# controller.net
KiCad netlist of a schematic drawn in EAGLE
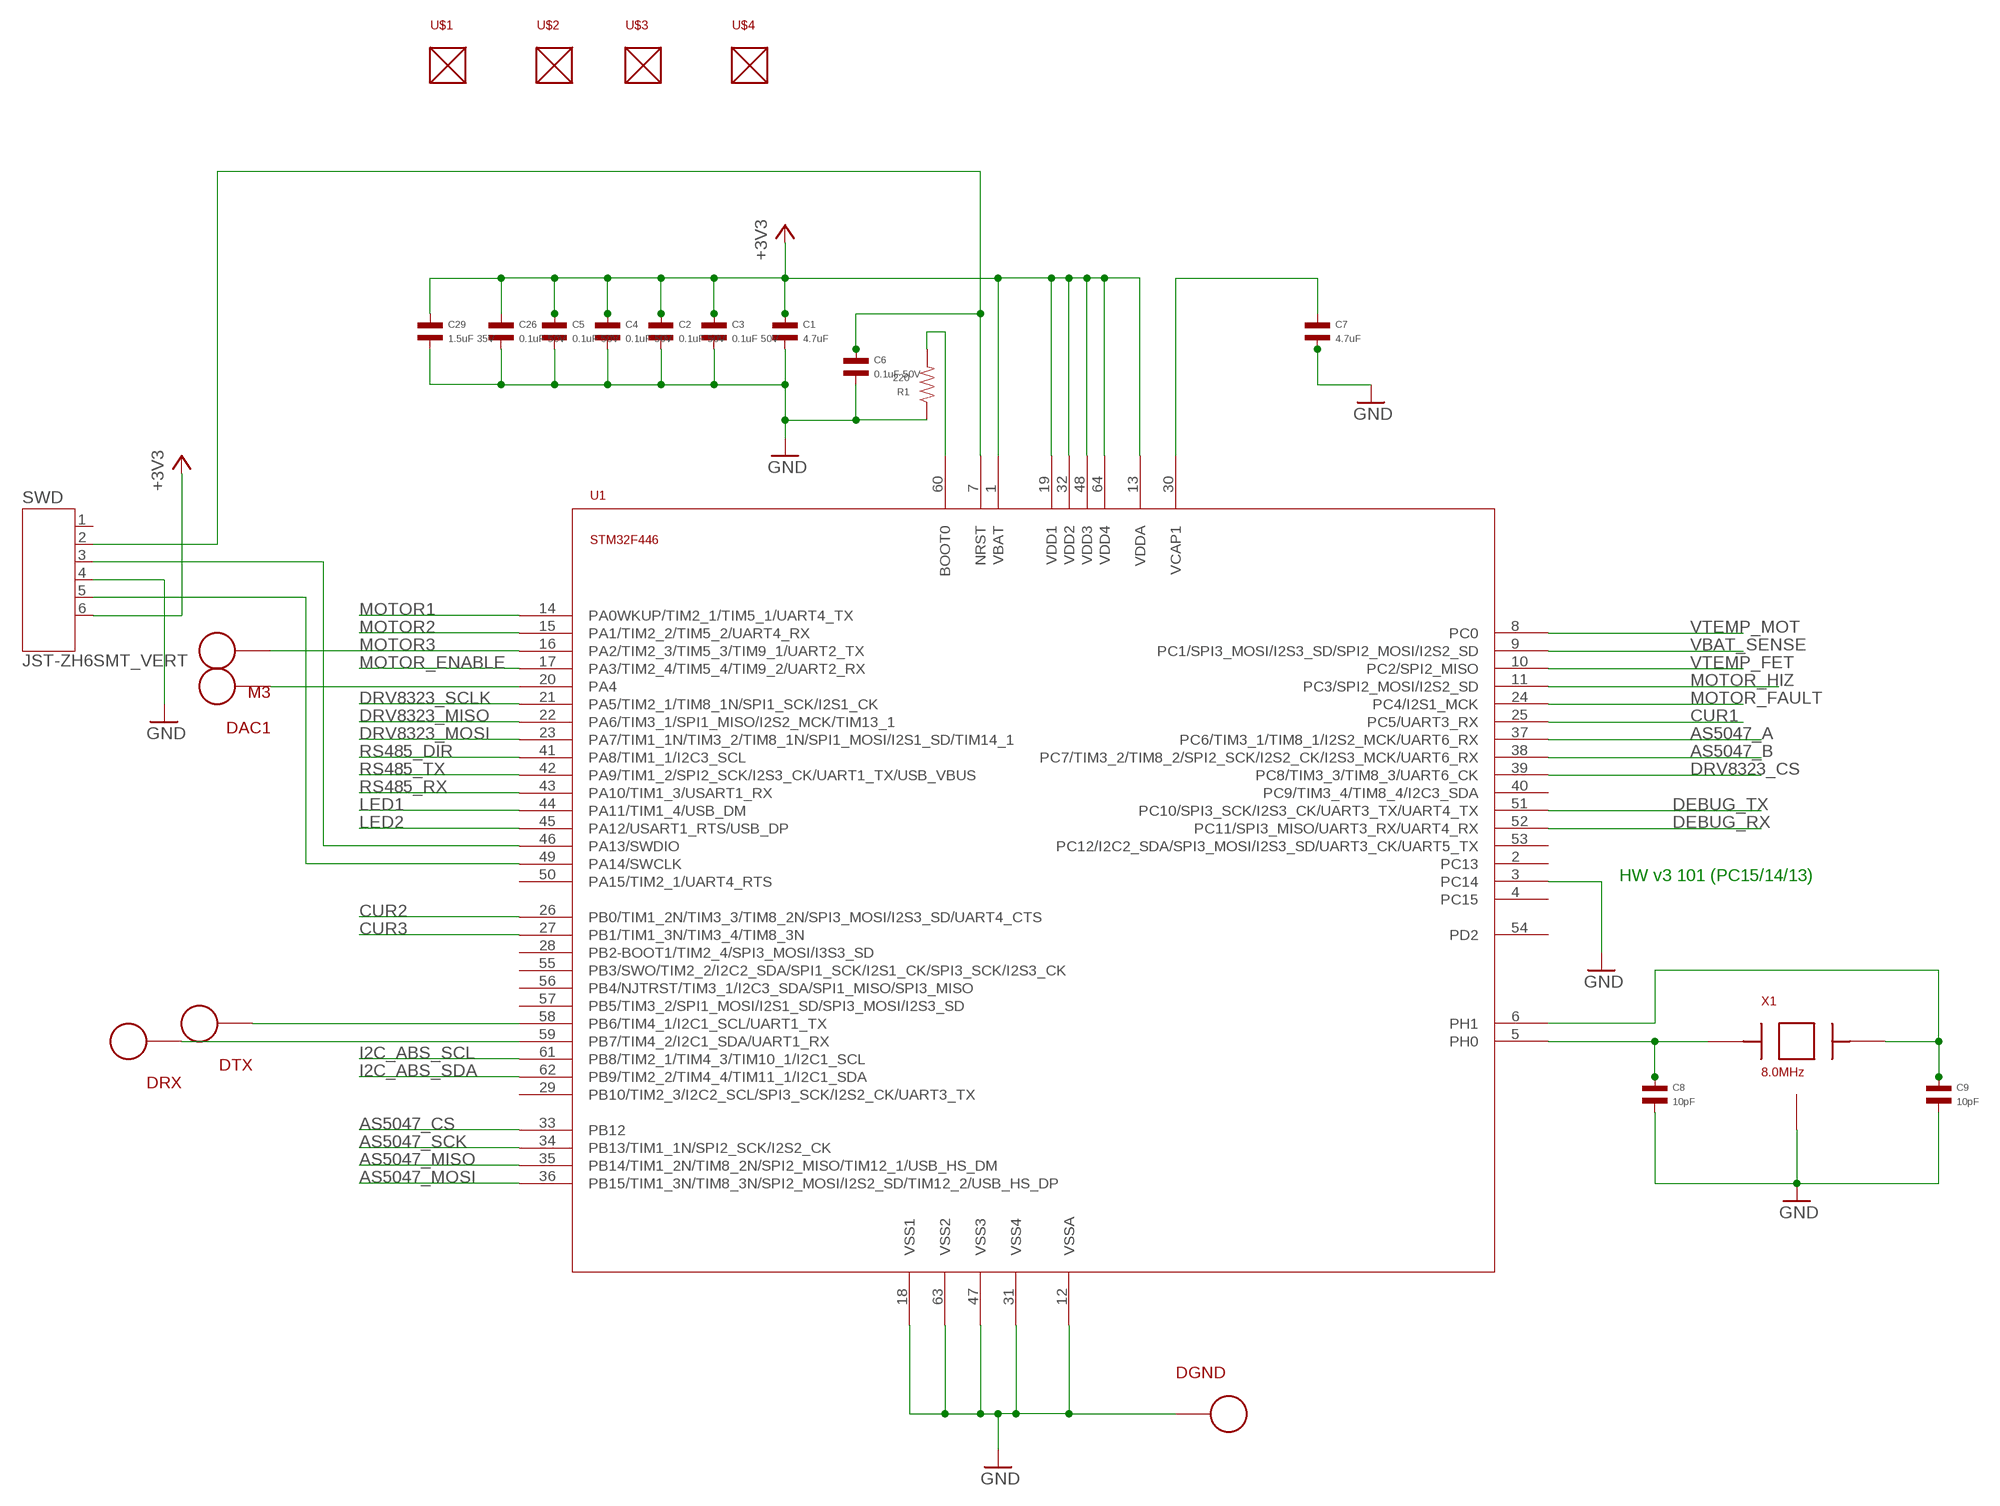
[diagram p0: schematic, sheet 1, part 1 of 2]
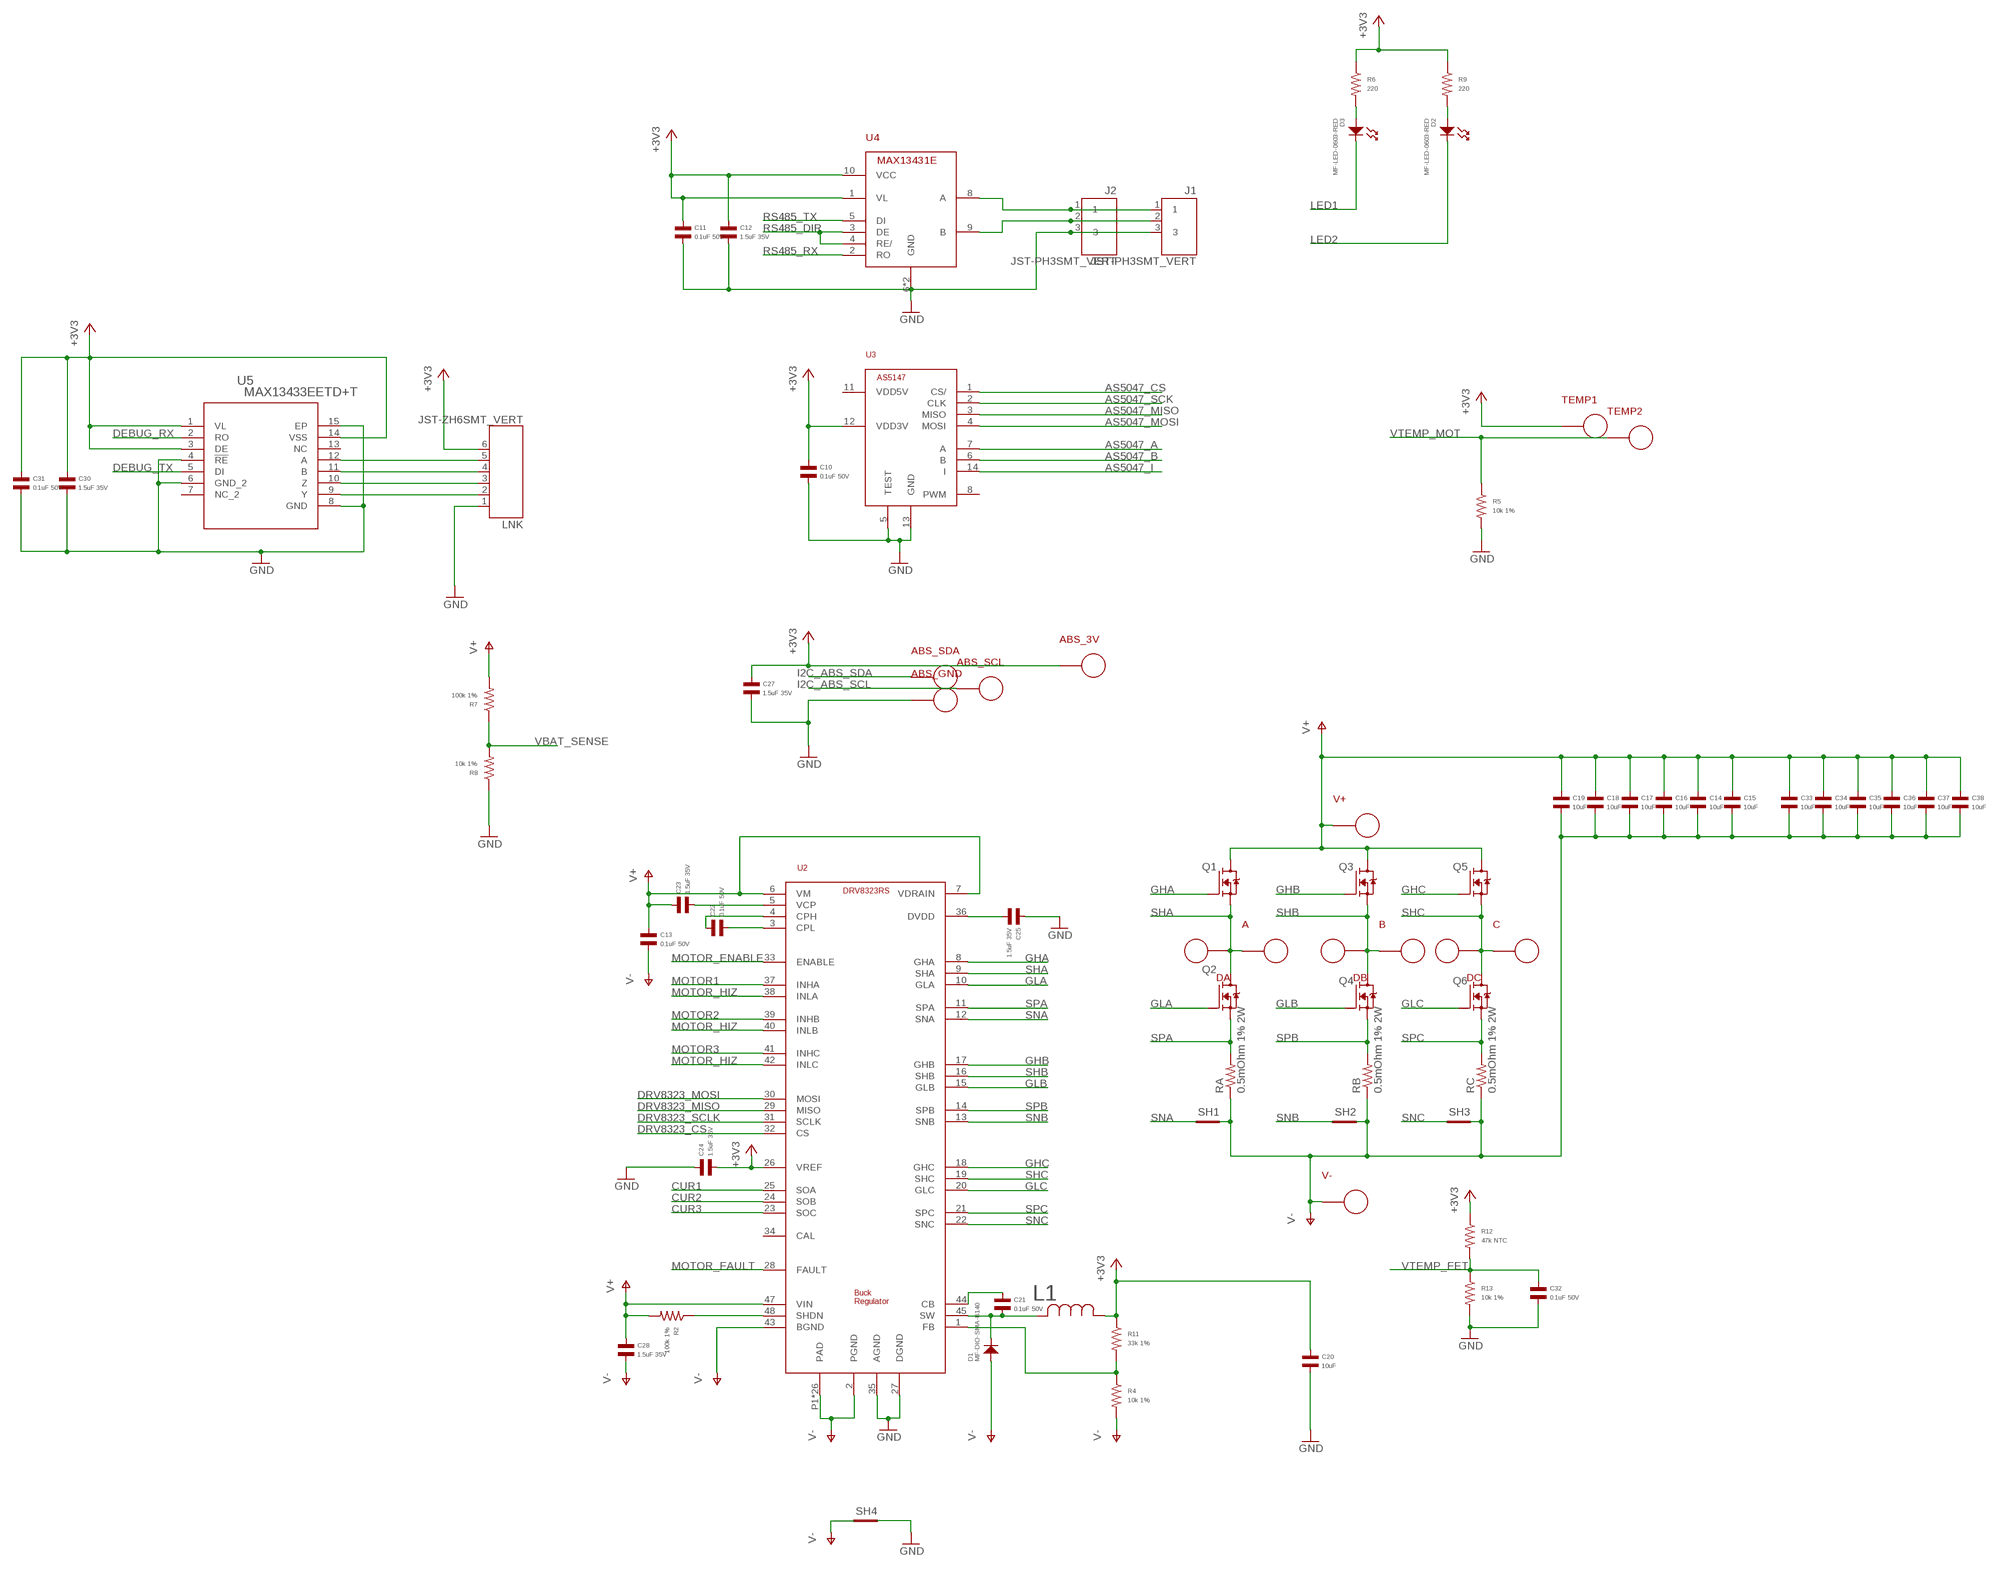
[diagram p1: schematic, sheet 1, part 2 of 2]

(export (version "E")
  (design (tool "Eeschema 10.0.6"))
  (components
    (comp (ref "A")
      (value "PAD")
      (footprint "eagle-import:18AWG_PAD")
      (libsource (lib "eagle-import") (part "PAD"))
    )
    (comp (ref "ABS_3V")
      (value "PAD24AWG_PAD")
      (footprint "eagle-import:24AWG_PAD")
      (libsource (lib "eagle-import") (part "PAD24AWG_PAD"))
    )
    (comp (ref "ABS_GND")
      (value "PAD24AWG_PAD")
      (footprint "eagle-import:24AWG_PAD")
      (libsource (lib "eagle-import") (part "PAD24AWG_PAD"))
    )
    (comp (ref "ABS_SCL")
      (value "PAD24AWG_PAD")
      (footprint "eagle-import:24AWG_PAD")
      (libsource (lib "eagle-import") (part "PAD24AWG_PAD"))
    )
    (comp (ref "ABS_SDA")
      (value "PAD24AWG_PAD")
      (footprint "eagle-import:24AWG_PAD")
      (libsource (lib "eagle-import") (part "PAD24AWG_PAD"))
    )
    (comp (ref "B")
      (value "PAD")
      (footprint "eagle-import:18AWG_PAD")
      (libsource (lib "eagle-import") (part "PAD"))
    )
    (comp (ref "C")
      (value "PAD")
      (footprint "eagle-import:18AWG_PAD")
      (libsource (lib "eagle-import") (part "PAD"))
    )
    (comp (ref "C1")
      (value "4.7uF")
      (footprint "eagle-import:C0603")
      (fields (field (name "MF") "Samsung Electro-Mechanics") (field (name "MPN") "CL10A475MP8NNNC"))
      (libsource (lib "eagle-import") (part "CAPACITOR_NP_0603"))
    )
    (comp (ref "C2")
      (value "0.1uF 50V")
      (footprint "eagle-import:C0402")
      (fields (field (name "MF") "TDK") (field (name "MPN") "CGA2B3X7R1H104K050BB"))
      (libsource (lib "eagle-import") (part "CAPACITOR_NP_0402"))
    )
    (comp (ref "C3")
      (value "0.1uF 50V")
      (footprint "eagle-import:C0402")
      (fields (field (name "MF") "TDK") (field (name "MPN") "CGA2B3X7R1H104K050BB"))
      (libsource (lib "eagle-import") (part "CAPACITOR_NP_0402"))
    )
    (comp (ref "C4")
      (value "0.1uF 50V")
      (footprint "eagle-import:C0402")
      (fields (field (name "MF") "TDK") (field (name "MPN") "CGA2B3X7R1H104K050BB"))
      (libsource (lib "eagle-import") (part "CAPACITOR_NP_0402"))
    )
    (comp (ref "C5")
      (value "0.1uF 50V")
      (footprint "eagle-import:C0402")
      (fields (field (name "MF") "TDK") (field (name "MPN") "CGA2B3X7R1H104K050BB"))
      (libsource (lib "eagle-import") (part "CAPACITOR_NP_0402"))
    )
    (comp (ref "C6")
      (value "0.1uF 50V")
      (footprint "eagle-import:C0402")
      (fields (field (name "MF") "TDK") (field (name "MPN") "CGA2B3X7R1H104K050BB"))
      (libsource (lib "eagle-import") (part "CAPACITOR_NP_0402"))
    )
    (comp (ref "C7")
      (value "4.7uF")
      (footprint "eagle-import:C0603")
      (fields (field (name "MF") "Samsung Electro-Mechanics") (field (name "MPN") "CL10A475MP8NNNC"))
      (libsource (lib "eagle-import") (part "CAPACITOR_NP_0603"))
    )
    (comp (ref "C8")
      (value "10pF")
      (footprint "eagle-import:C0402")
      (fields (field (name "MF") "Samsung Electro-Mechanics") (field (name "MPN") "CL05C100JB51PNC"))
      (libsource (lib "eagle-import") (part "CAPACITOR_NP_0402"))
    )
    (comp (ref "C9")
      (value "10pF")
      (footprint "eagle-import:C0402")
      (fields (field (name "MF") "Samsung Electro-Mechanics") (field (name "MPN") "CL05C100JB51PNC"))
      (libsource (lib "eagle-import") (part "CAPACITOR_NP_0402"))
    )
    (comp (ref "C10")
      (value "0.1uF 50V")
      (footprint "eagle-import:C0402")
      (fields (field (name "MF") "TDK") (field (name "MPN") "CGA2B3X7R1H104K050BB"))
      (libsource (lib "eagle-import") (part "CAPACITOR_NP_0402"))
    )
    (comp (ref "C11")
      (value "0.1uF 50V")
      (footprint "eagle-import:C0402")
      (fields (field (name "MF") "TDK") (field (name "MPN") "CGA2B3X7R1H104K050BB"))
      (libsource (lib "eagle-import") (part "CAPACITOR_NP_0402"))
    )
    (comp (ref "C12")
      (value "1.5uF 35V")
      (footprint "eagle-import:C0402")
      (fields (field (name "MF") "TDK") (field (name "MPN") "C1005X5R1V155M050BC"))
      (libsource (lib "eagle-import") (part "CAPACITOR_NP_0402"))
    )
    (comp (ref "C13")
      (value "0.1uF 50V")
      (footprint "eagle-import:C0402")
      (fields (field (name "MF") "TDK") (field (name "MPN") "CGA2B3X7R1H104K050BB"))
      (libsource (lib "eagle-import") (part "CAPACITOR_NP_0402"))
    )
    (comp (ref "C14")
      (value "10uF")
      (footprint "eagle-import:C1206")
      (fields (field (name "MF") "TDK") (field (name "MPN") "CGA5L1X7R1V106K160AC"))
      (libsource (lib "eagle-import") (part "CAPACITOR_NP_1206"))
    )
    (comp (ref "C15")
      (value "10uF")
      (footprint "eagle-import:C1206")
      (fields (field (name "MF") "TDK") (field (name "MPN") "CGA5L1X7R1V106K160AC"))
      (libsource (lib "eagle-import") (part "CAPACITOR_NP_1206"))
    )
    (comp (ref "C16")
      (value "10uF")
      (footprint "eagle-import:C1206")
      (fields (field (name "MF") "TDK") (field (name "MPN") "CGA5L1X7R1V106K160AC"))
      (libsource (lib "eagle-import") (part "CAPACITOR_NP_1206"))
    )
    (comp (ref "C17")
      (value "10uF")
      (footprint "eagle-import:C1206")
      (fields (field (name "MF") "TDK") (field (name "MPN") "CGA5L1X7R1V106K160AC"))
      (libsource (lib "eagle-import") (part "CAPACITOR_NP_1206"))
    )
    (comp (ref "C18")
      (value "10uF")
      (footprint "eagle-import:C1206")
      (fields (field (name "MF") "TDK") (field (name "MPN") "CGA5L1X7R1V106K160AC"))
      (libsource (lib "eagle-import") (part "CAPACITOR_NP_1206"))
    )
    (comp (ref "C19")
      (value "10uF")
      (footprint "eagle-import:C1206")
      (fields (field (name "MF") "TDK") (field (name "MPN") "CGA5L1X7R1V106K160AC"))
      (libsource (lib "eagle-import") (part "CAPACITOR_NP_1206"))
    )
    (comp (ref "C20")
      (value "10uF")
      (footprint "eagle-import:C1206")
      (fields (field (name "MF") "TDK") (field (name "MPN") "CGA5L1X7R1V106K160AC"))
      (libsource (lib "eagle-import") (part "CAPACITOR_NP_1206"))
    )
    (comp (ref "C21")
      (value "0.1uF 50V")
      (footprint "eagle-import:C0402")
      (fields (field (name "MF") "TDK") (field (name "MPN") "CGA2B3X7R1H104K050BB"))
      (libsource (lib "eagle-import") (part "CAPACITOR_NP_0402"))
    )
    (comp (ref "C22")
      (value "0.1uF 50V")
      (footprint "eagle-import:C0402")
      (fields (field (name "MF") "TDK") (field (name "MPN") "CGA2B3X7R1H104K050BB"))
      (libsource (lib "eagle-import") (part "CAPACITOR_NP_0402"))
    )
    (comp (ref "C23")
      (value "1.5uF 35V")
      (footprint "eagle-import:C0402")
      (fields (field (name "MF") "TDK") (field (name "MPN") "C1005X5R1V155M050BC"))
      (libsource (lib "eagle-import") (part "CAPACITOR_NP_0402"))
    )
    (comp (ref "C24")
      (value "1.5uF 35V")
      (footprint "eagle-import:C0402")
      (fields (field (name "MF") "TDK") (field (name "MPN") "C1005X5R1V155M050BC"))
      (libsource (lib "eagle-import") (part "CAPACITOR_NP_0402"))
    )
    (comp (ref "C25")
      (value "1.5uF 35V")
      (footprint "eagle-import:C0402")
      (fields (field (name "MF") "TDK") (field (name "MPN") "C1005X5R1V155M050BC"))
      (libsource (lib "eagle-import") (part "CAPACITOR_NP_0402"))
    )
    (comp (ref "C26")
      (value "0.1uF 50V")
      (footprint "eagle-import:C0402")
      (fields (field (name "MF") "TDK") (field (name "MPN") "CGA2B3X7R1H104K050BB"))
      (libsource (lib "eagle-import") (part "CAPACITOR_NP_0402"))
    )
    (comp (ref "C27")
      (value "1.5uF 35V")
      (footprint "eagle-import:C0402")
      (fields (field (name "MF") "TDK") (field (name "MPN") "C1005X5R1V155M050BC"))
      (libsource (lib "eagle-import") (part "CAPACITOR_NP_0402"))
    )
    (comp (ref "C28")
      (value "1.5uF 35V")
      (footprint "eagle-import:C0402")
      (fields (field (name "MF") "TDK") (field (name "MPN") "C1005X5R1V155M050BC"))
      (libsource (lib "eagle-import") (part "CAPACITOR_NP_0402"))
    )
    (comp (ref "C29")
      (value "1.5uF 35V")
      (footprint "eagle-import:C0402")
      (fields (field (name "MF") "TDK") (field (name "MPN") "C1005X5R1V155M050BC"))
      (libsource (lib "eagle-import") (part "CAPACITOR_NP_0402"))
    )
    (comp (ref "C30")
      (value "1.5uF 35V")
      (footprint "eagle-import:C0402")
      (fields (field (name "MF") "TDK") (field (name "MPN") "C1005X5R1V155M050BC"))
      (libsource (lib "eagle-import") (part "CAPACITOR_NP_0402"))
    )
    (comp (ref "C31")
      (value "0.1uF 50V")
      (footprint "eagle-import:C0402")
      (fields (field (name "MF") "TDK") (field (name "MPN") "CGA2B3X7R1H104K050BB"))
      (libsource (lib "eagle-import") (part "CAPACITOR_NP_0402"))
    )
    (comp (ref "C32")
      (value "0.1uF 50V")
      (footprint "eagle-import:C0402")
      (fields (field (name "MF") "TDK") (field (name "MPN") "CGA2B3X7R1H104K050BB"))
      (libsource (lib "eagle-import") (part "CAPACITOR_NP_0402"))
    )
    (comp (ref "C33")
      (value "10uF")
      (footprint "eagle-import:C1206")
      (fields (field (name "MF") "TDK") (field (name "MPN") "CGA5L1X7R1V106K160AC"))
      (libsource (lib "eagle-import") (part "CAPACITOR_NP_1206"))
    )
    (comp (ref "C34")
      (value "10uF")
      (footprint "eagle-import:C1206")
      (fields (field (name "MF") "TDK") (field (name "MPN") "CGA5L1X7R1V106K160AC"))
      (libsource (lib "eagle-import") (part "CAPACITOR_NP_1206"))
    )
    (comp (ref "C35")
      (value "10uF")
      (footprint "eagle-import:C1206")
      (fields (field (name "MF") "TDK") (field (name "MPN") "CGA5L1X7R1V106K160AC"))
      (libsource (lib "eagle-import") (part "CAPACITOR_NP_1206"))
    )
    (comp (ref "C36")
      (value "10uF")
      (footprint "eagle-import:C1206")
      (fields (field (name "MF") "TDK") (field (name "MPN") "CGA5L1X7R1V106K160AC"))
      (libsource (lib "eagle-import") (part "CAPACITOR_NP_1206"))
    )
    (comp (ref "C37")
      (value "10uF")
      (footprint "eagle-import:C1206")
      (fields (field (name "MF") "TDK") (field (name "MPN") "CGA5L1X7R1V106K160AC"))
      (libsource (lib "eagle-import") (part "CAPACITOR_NP_1206"))
    )
    (comp (ref "C38")
      (value "10uF")
      (footprint "eagle-import:C1206")
      (fields (field (name "MF") "TDK") (field (name "MPN") "CGA5L1X7R1V106K160AC"))
      (libsource (lib "eagle-import") (part "CAPACITOR_NP_1206"))
    )
    (comp (ref "D1")
      (value "MF-DIO-SMA-B140")
      (footprint "eagle-import:SMA")
      (fields (field (name "HOUSEPART") "YES"))
      (libsource (lib "eagle-import") (part "DIODES_SMA_B140"))
    )
    (comp (ref "D2")
      (value "MF-LED-0603-RED")
      (footprint "eagle-import:LED0603")
      (fields (field (name "HOUSEPART") "YES"))
      (libsource (lib "eagle-import") (part "LED_SINGLE-0603-RED"))
    )
    (comp (ref "D3")
      (value "MF-LED-0603-RED")
      (footprint "eagle-import:LED0603")
      (fields (field (name "HOUSEPART") "YES"))
      (libsource (lib "eagle-import") (part "LED_SINGLE-0603-RED"))
    )
    (comp (ref "DA")
      (value "PAD24AWG_PAD")
      (footprint "eagle-import:24AWG_PAD")
      (libsource (lib "eagle-import") (part "PAD24AWG_PAD"))
    )
    (comp (ref "DAC1")
      (value "PAD24AWG_PAD")
      (footprint "eagle-import:24AWG_PAD")
      (libsource (lib "eagle-import") (part "PAD24AWG_PAD"))
    )
    (comp (ref "DB")
      (value "PAD24AWG_PAD")
      (footprint "eagle-import:24AWG_PAD")
      (libsource (lib "eagle-import") (part "PAD24AWG_PAD"))
    )
    (comp (ref "DC")
      (value "PAD24AWG_PAD")
      (footprint "eagle-import:24AWG_PAD")
      (libsource (lib "eagle-import") (part "PAD24AWG_PAD"))
    )
    (comp (ref "DGND")
      (value "PAD24AWG_PAD")
      (footprint "eagle-import:24AWG_PAD")
      (libsource (lib "eagle-import") (part "PAD24AWG_PAD"))
    )
    (comp (ref "DRX")
      (value "PAD24AWG_PAD")
      (footprint "eagle-import:24AWG_PAD")
      (libsource (lib "eagle-import") (part "PAD24AWG_PAD"))
    )
    (comp (ref "DTX")
      (value "PAD24AWG_PAD")
      (footprint "eagle-import:24AWG_PAD")
      (libsource (lib "eagle-import") (part "PAD24AWG_PAD"))
    )
    (comp (ref "J1")
      (value "JST-PH3SMT_VERT")
      (footprint "eagle-import:JST_B3B_PH-SM4-TB(LF)(SN)")
      (fields (field (name "MF") "JST") (field (name "MPN") "B3B-PH-SM4-TB(LF)(SN)"))
      (libsource (lib "eagle-import") (part "JST-PH3SMT_VERT"))
    )
    (comp (ref "J2")
      (value "JST-PH3SMT_VERT")
      (footprint "eagle-import:JST_B3B_PH-SM4-TB(LF)(SN)")
      (fields (field (name "MF") "JST") (field (name "MPN") "B3B-PH-SM4-TB(LF)(SN)"))
      (libsource (lib "eagle-import") (part "JST-PH3SMT_VERT"))
    )
    (comp (ref "L1")
      (value "SRN4018-220M")
      (footprint "eagle-import:IND_BOURNS_SRN4018")
      (fields (field (name "MANUFACTURER_PART_NUMBER") "SRN4018220M"))
      (libsource (lib "eagle-import") (part "SRN4018-220M"))
    )
    (comp (ref "LNK")
      (value "JST-ZH6SMT_VERT")
      (footprint "eagle-import:JST_B6B-ZR-SM4-TF(LF)(SN)")
      (fields (field (name "MF") "JST") (field (name "MPN") "B6B-ZR-SM4-TF(LF)(SN)"))
      (libsource (lib "eagle-import") (part "JST-ZH6SMT_VERT"))
    )
    (comp (ref "M3")
      (value "PAD24AWG_PAD")
      (footprint "eagle-import:24AWG_PAD")
      (libsource (lib "eagle-import") (part "PAD24AWG_PAD"))
    )
    (comp (ref "Q1")
      (value "TPN1R603PL")
      (footprint "eagle-import:TSON_ADVANCE_8")
      (fields (field (name "MF") "Toshiba") (field (name "MPN") "TPN1R603PL,L1Q"))
      (libsource (lib "eagle-import") (part "TPN1R603PL"))
    )
    (comp (ref "Q2")
      (value "TPN1R603PL")
      (footprint "eagle-import:TSON_ADVANCE_8")
      (fields (field (name "MF") "Toshiba") (field (name "MPN") "TPN1R603PL,L1Q"))
      (libsource (lib "eagle-import") (part "TPN1R603PL"))
    )
    (comp (ref "Q3")
      (value "TPN1R603PL")
      (footprint "eagle-import:TSON_ADVANCE_8")
      (fields (field (name "MF") "Toshiba") (field (name "MPN") "TPN1R603PL,L1Q"))
      (libsource (lib "eagle-import") (part "TPN1R603PL"))
    )
    (comp (ref "Q4")
      (value "TPN1R603PL")
      (footprint "eagle-import:TSON_ADVANCE_8")
      (fields (field (name "MF") "Toshiba") (field (name "MPN") "TPN1R603PL,L1Q"))
      (libsource (lib "eagle-import") (part "TPN1R603PL"))
    )
    (comp (ref "Q5")
      (value "TPN1R603PL")
      (footprint "eagle-import:TSON_ADVANCE_8")
      (fields (field (name "MF") "Toshiba") (field (name "MPN") "TPN1R603PL,L1Q"))
      (libsource (lib "eagle-import") (part "TPN1R603PL"))
    )
    (comp (ref "Q6")
      (value "TPN1R603PL")
      (footprint "eagle-import:TSON_ADVANCE_8")
      (fields (field (name "MF") "Toshiba") (field (name "MPN") "TPN1R603PL,L1Q"))
      (libsource (lib "eagle-import") (part "TPN1R603PL"))
    )
    (comp (ref "R1")
      (value "220")
      (footprint "eagle-import:R0402")
      (fields (field (name "HOUSEPART") "1") (field (name "MPN") "MF-RES-0402-220"))
      (libsource (lib "eagle-import") (part "RESISTOR_0402"))
    )
    (comp (ref "R2")
      (value "100k 1%")
      (footprint "eagle-import:R0402")
      (fields (field (name "MF") "Panasonic") (field (name "MPN") "ERJ-2RKF1003X"))
      (libsource (lib "eagle-import") (part "RESISTOR_0402"))
    )
    (comp (ref "R4")
      (value "10k 1%")
      (footprint "eagle-import:R0402")
      (fields (field (name "MF") "Panasonic") (field (name "MPN") "ERJ-2RKF1002X"))
      (libsource (lib "eagle-import") (part "RESISTOR_0402"))
    )
    (comp (ref "R5")
      (value "10k 1%")
      (footprint "eagle-import:R0402")
      (fields (field (name "MF") "Panasonic") (field (name "MPN") "ERJ-2RKF1002X"))
      (libsource (lib "eagle-import") (part "RESISTOR_0402"))
    )
    (comp (ref "R6")
      (value "220")
      (footprint "eagle-import:R0402")
      (fields (field (name "HOUSEPART") "1") (field (name "MPN") "MF-RES-0402-220"))
      (libsource (lib "eagle-import") (part "RESISTOR_0402"))
    )
    (comp (ref "R7")
      (value "100k 1%")
      (footprint "eagle-import:R0402")
      (fields (field (name "MF") "Panasonic") (field (name "MPN") "ERJ-2RKF1003X"))
      (libsource (lib "eagle-import") (part "RESISTOR_0402"))
    )
    (comp (ref "R8")
      (value "10k 1%")
      (footprint "eagle-import:R0402")
      (fields (field (name "MF") "Panasonic") (field (name "MPN") "ERJ-2RKF1002X"))
      (libsource (lib "eagle-import") (part "RESISTOR_0402"))
    )
    (comp (ref "R9")
      (value "220")
      (footprint "eagle-import:R0402")
      (fields (field (name "HOUSEPART") "1") (field (name "MPN") "MF-RES-0402-220"))
      (libsource (lib "eagle-import") (part "RESISTOR_0402"))
    )
    (comp (ref "R11")
      (value "33k 1%")
      (footprint "eagle-import:R0402")
      (fields (field (name "MF") "Panasonic") (field (name "MPN") "ERJ-2RKF3302X"))
      (libsource (lib "eagle-import") (part "RESISTOR_0402"))
    )
    (comp (ref "R12")
      (value "47k NTC")
      (footprint "eagle-import:R0402")
      (fields (field (name "MF") "Murata") (field (name "MPN") "NCP15WB473F03RC"))
      (libsource (lib "eagle-import") (part "RESISTOR_0402"))
    )
    (comp (ref "R13")
      (value "10k 1%")
      (footprint "eagle-import:R0402")
      (fields (field (name "MF") "Panasonic") (field (name "MPN") "ERJ-2RKF1002X"))
      (libsource (lib "eagle-import") (part "RESISTOR_0402"))
    )
    (comp (ref "RA")
      (value "0.5mOhm 1% 2W")
      (footprint "eagle-import:M1206")
      (fields (field (name "MF") "Stackpole Electronics") (field (name "MPN") "HCS1206FTL500"))
      (libsource (lib "eagle-import") (part "R-US_M1206"))
    )
    (comp (ref "RB")
      (value "0.5mOhm 1% 2W")
      (footprint "eagle-import:M1206")
      (fields (field (name "MF") "Stackpole Electronics") (field (name "MPN") "HCS1206FTL500"))
      (libsource (lib "eagle-import") (part "R-US_M1206"))
    )
    (comp (ref "RC")
      (value "0.5mOhm 1% 2W")
      (footprint "eagle-import:M1206")
      (fields (field (name "MF") "Stackpole Electronics") (field (name "MPN") "HCS1206FTL500"))
      (libsource (lib "eagle-import") (part "R-US_M1206"))
    )
    (comp (ref "SH1")
      (value "SHORTT5")
      (footprint "eagle-import:SHORT_TOP-50")
      (libsource (lib "eagle-import") (part "SHORTT5"))
    )
    (comp (ref "SH2")
      (value "SHORTT5")
      (footprint "eagle-import:SHORT_TOP-50")
      (libsource (lib "eagle-import") (part "SHORTT5"))
    )
    (comp (ref "SH3")
      (value "SHORTT5")
      (footprint "eagle-import:SHORT_TOP-50")
      (libsource (lib "eagle-import") (part "SHORTT5"))
    )
    (comp (ref "SH4")
      (value "SHORTBIG")
      (footprint "eagle-import:SHORT_TOP-BIG")
      (libsource (lib "eagle-import") (part "SHORTBIG"))
    )
    (comp (ref "SWD")
      (value "JST-ZH6SMT_VERT")
      (footprint "eagle-import:JST_B6B-ZR-SM4-TF(LF)(SN)")
      (fields (field (name "MF") "JST") (field (name "MPN") "B6B-ZR-SM4-TF(LF)(SN)"))
      (libsource (lib "eagle-import") (part "JST-ZH6SMT_VERT"))
    )
    (comp (ref "TEMP1")
      (value "PAD24AWG_PAD")
      (footprint "eagle-import:24AWG_PAD")
      (libsource (lib "eagle-import") (part "PAD24AWG_PAD"))
    )
    (comp (ref "TEMP2")
      (value "PAD24AWG_PAD")
      (footprint "eagle-import:24AWG_PAD")
      (libsource (lib "eagle-import") (part "PAD24AWG_PAD"))
    )
    (comp (ref "U$1")
      (value "MOUNTM2")
      (footprint "eagle-import:M2MOUNT")
      (libsource (lib "eagle-import") (part "MOUNTM2"))
    )
    (comp (ref "U$2")
      (value "MOUNTM2")
      (footprint "eagle-import:M2MOUNT")
      (libsource (lib "eagle-import") (part "MOUNTM2"))
    )
    (comp (ref "U$3")
      (value "MOUNTM2")
      (footprint "eagle-import:M2MOUNT")
      (libsource (lib "eagle-import") (part "MOUNTM2"))
    )
    (comp (ref "U$4")
      (value "MOUNTM2")
      (footprint "eagle-import:M2MOUNT")
      (libsource (lib "eagle-import") (part "MOUNTM2"))
    )
    (comp (ref "U1")
      (value "STM32F4R_64PIN")
      (footprint "eagle-import:LQFP64")
      (fields (field (name "MF") "ST") (field (name "MPN") "STM32F446RET6"))
      (libsource (lib "eagle-import") (part "STM32F4R_64PIN"))
    )
    (comp (ref "U2")
      (value "DRV8323RS")
      (footprint "eagle-import:PVQFN-N48")
      (fields (field (name "MF") "TI") (field (name "MPN") "DRV8323RSRGZR"))
      (libsource (lib "eagle-import") (part "DRV8323RS"))
    )
    (comp (ref "U3")
      (value "AS5147")
      (footprint "eagle-import:TSSOP14")
      (fields (field (name "MF") "AMS") (field (name "MPN") "AS5047P-ATSM"))
      (libsource (lib "eagle-import") (part "AS5147"))
    )
    (comp (ref "U4")
      (value "MAX13431E")
      (footprint "eagle-import:TDFN10")
      (fields (field (name "MF") "Maxim") (field (name "MPN") "MAX13431EETB+T"))
      (libsource (lib "eagle-import") (part "MAX13431E"))
    )
    (comp (ref "U5")
      (value "MAX13433EETD+T")
      (footprint "eagle-import:21-0137I_T1433-1")
      (fields (field (name "MF") "Maxim"))
      (libsource (lib "eagle-import") (part "MAX13433EETD+T"))
    )
    (comp (ref "V+")
      (value "PAD12AWG_PAD")
      (footprint "eagle-import:12AWG_PAD")
      (libsource (lib "eagle-import") (part "PAD12AWG_PAD"))
    )
    (comp (ref "V-")
      (value "PAD12AWG_PAD")
      (footprint "eagle-import:12AWG_PAD")
      (libsource (lib "eagle-import") (part "PAD12AWG_PAD"))
    )
    (comp (ref "X1")
      (value "8.0MHz")
      (footprint "eagle-import:ABM3B")
      (fields (field (name "MF") "Abracon") (field (name "MPN") "ABM3B-8.000MHZ-10-1-U-T"))
      (libsource (lib "eagle-import") (part "CRYSTALABM3B"))
    )
  )
  (nets
    (net (code "1") (name "+3V3") (class "Default")
      (node (ref "ABS_3V") (pin "P$1") (pinfunction "P$1_P$1") (pintype "bidirectional"))
      (node (ref "C1") (pin "P$1") (pinfunction "P$1_P$1") (pintype "passive"))
      (node (ref "C10") (pin "P$1") (pinfunction "P$1_P$1") (pintype "passive"))
      (node (ref "C11") (pin "P$1") (pinfunction "P$1_P$1") (pintype "passive"))
      (node (ref "C12") (pin "P$1") (pinfunction "P$1_P$1") (pintype "passive"))
      (node (ref "C2") (pin "P$1") (pinfunction "P$1_P$1") (pintype "passive"))
      (node (ref "C20") (pin "P$1") (pinfunction "P$1_P$1") (pintype "passive"))
      (node (ref "C24") (pin "P$2") (pinfunction "P$2_P$2") (pintype "passive"))
      (node (ref "C26") (pin "P$1") (pinfunction "P$1_P$1") (pintype "passive"))
      (node (ref "C27") (pin "P$1") (pinfunction "P$1_P$1") (pintype "passive"))
      (node (ref "C29") (pin "P$1") (pinfunction "P$1_P$1") (pintype "passive"))
      (node (ref "C3") (pin "P$1") (pinfunction "P$1_P$1") (pintype "passive"))
      (node (ref "C30") (pin "P$1") (pinfunction "P$1_P$1") (pintype "passive"))
      (node (ref "C31") (pin "P$1") (pinfunction "P$1_P$1") (pintype "passive"))
      (node (ref "C4") (pin "P$1") (pinfunction "P$1_P$1") (pintype "passive"))
      (node (ref "C5") (pin "P$1") (pinfunction "P$1_P$1") (pintype "passive"))
      (node (ref "L1") (pin "1") (pinfunction "1_1") (pintype "passive"))
      (node (ref "LNK") (pin "6") (pinfunction "6_6") (pintype "passive"))
      (node (ref "R11") (pin "P$1") (pinfunction "P$1_P$1") (pintype "passive"))
      (node (ref "R12") (pin "P$1") (pinfunction "P$1_P$1") (pintype "passive"))
      (node (ref "R6") (pin "P$1") (pinfunction "P$1_P$1") (pintype "passive"))
      (node (ref "R9") (pin "P$1") (pinfunction "P$1_P$1") (pintype "passive"))
      (node (ref "SWD") (pin "6") (pinfunction "6_6") (pintype "passive"))
      (node (ref "TEMP1") (pin "P$1") (pinfunction "P$1_P$1") (pintype "bidirectional"))
      (node (ref "U1") (pin "1") (pinfunction "VBAT_1") (pintype "bidirectional"))
      (node (ref "U1") (pin "13") (pinfunction "VDDA_13") (pintype "bidirectional"))
      (node (ref "U1") (pin "19") (pinfunction "VDD1_19") (pintype "bidirectional"))
      (node (ref "U1") (pin "32") (pinfunction "VDD2_32") (pintype "bidirectional"))
      (node (ref "U1") (pin "48") (pinfunction "VDD3_48") (pintype "bidirectional"))
      (node (ref "U1") (pin "64") (pinfunction "VDD4_64") (pintype "bidirectional"))
      (node (ref "U2") (pin "26") (pinfunction "VREF_26") (pintype "bidirectional"))
      (node (ref "U3") (pin "12") (pinfunction "VDD3V_12") (pintype "bidirectional"))
      (node (ref "U4") (pin "1") (pinfunction "VL_1") (pintype "bidirectional"))
      (node (ref "U4") (pin "10") (pinfunction "VCC_10") (pintype "bidirectional"))
      (node (ref "U5") (pin "1") (pinfunction "VL_1") (pintype "power_in"))
      (node (ref "U5") (pin "14") (pinfunction "VSS_14") (pintype "power_in"))
      (node (ref "U5") (pin "3") (pinfunction "DE_3") (pintype "input"))
    )
    (net (code "2") (name "/AS5047_A") (class "Default")
      (node (ref "U1") (pin "37") (pinfunction "PC6/TIM3_1/TIM8_1/I2S2_MCK/UART6_RX_37") (pintype "bidirectional"))
      (node (ref "U3") (pin "7") (pinfunction "A_7") (pintype "bidirectional"))
    )
    (net (code "3") (name "/AS5047_B") (class "Default")
      (node (ref "U1") (pin "38") (pinfunction "PC7/TIM3_2/TIM8_2/SPI2_SCK/I2S2_CK/I2S3_MCK/UART6_RX_38") (pintype "bidirectional"))
      (node (ref "U3") (pin "6") (pinfunction "B_6") (pintype "bidirectional"))
    )
    (net (code "4") (name "/AS5047_CS") (class "Default")
      (node (ref "U1") (pin "33") (pinfunction "PB12_33") (pintype "bidirectional"))
      (node (ref "U3") (pin "1") (pinfunction "CS/_1") (pintype "bidirectional"))
    )
    (net (code "5") (name "/AS5047_I") (class "Default")
      (node (ref "U3") (pin "14") (pinfunction "I_14") (pintype "bidirectional"))
    )
    (net (code "6") (name "/AS5047_MISO") (class "Default")
      (node (ref "U1") (pin "35") (pinfunction "PB14/TIM1_2N/TIM8_2N/SPI2_MISO/TIM12_1/USB_HS_DM_35") (pintype "bidirectional"))
      (node (ref "U3") (pin "3") (pinfunction "MISO_3") (pintype "bidirectional"))
    )
    (net (code "7") (name "/AS5047_MOSI") (class "Default")
      (node (ref "U1") (pin "36") (pinfunction "PB15/TIM1_3N/TIM8_3N/SPI2_MOSI/I2S2_SD/TIM12_2/USB_HS_DP_36") (pintype "bidirectional"))
      (node (ref "U3") (pin "4") (pinfunction "MOSI_4") (pintype "bidirectional"))
    )
    (net (code "8") (name "/AS5047_SCK") (class "Default")
      (node (ref "U1") (pin "34") (pinfunction "PB13/TIM1_1N/SPI2_SCK/I2S2_CK_34") (pintype "bidirectional"))
      (node (ref "U3") (pin "2") (pinfunction "CLK_2") (pintype "bidirectional"))
    )
    (net (code "9") (name "/CUR1") (class "Default")
      (node (ref "U1") (pin "25") (pinfunction "PC5/UART3_RX_25") (pintype "bidirectional"))
      (node (ref "U2") (pin "25") (pinfunction "SOA_25") (pintype "bidirectional"))
    )
    (net (code "10") (name "/CUR2") (class "Default")
      (node (ref "U1") (pin "26") (pinfunction "PB0/TIM1_2N/TIM3_3/TIM8_2N/SPI3_MOSI/I2S3_SD/UART4_CTS_26") (pintype "bidirectional"))
      (node (ref "U2") (pin "24") (pinfunction "SOB_24") (pintype "bidirectional"))
    )
    (net (code "11") (name "/CUR3") (class "Default")
      (node (ref "U1") (pin "27") (pinfunction "PB1/TIM1_3N/TIM3_4/TIM8_3N_27") (pintype "bidirectional"))
      (node (ref "U2") (pin "23") (pinfunction "SOC_23") (pintype "bidirectional"))
    )
    (net (code "12") (name "/DEBUG_RX") (class "Default")
      (node (ref "U1") (pin "52") (pinfunction "PC11/SPI3_MISO/UART3_RX/UART4_RX_52") (pintype "bidirectional"))
      (node (ref "U5") (pin "2") (pinfunction "RO_2") (pintype "output"))
    )
    (net (code "13") (name "/DEBUG_TX") (class "Default")
      (node (ref "U1") (pin "51") (pinfunction "PC10/SPI3_SCK/I2S3_CK/UART3_TX/UART4_TX_51") (pintype "bidirectional"))
      (node (ref "U5") (pin "5") (pinfunction "DI_5") (pintype "input"))
    )
    (net (code "14") (name "/DRV8323_CS") (class "Default")
      (node (ref "U1") (pin "39") (pinfunction "PC8/TIM3_3/TIM8_3/UART6_CK_39") (pintype "bidirectional"))
      (node (ref "U2") (pin "32") (pinfunction "CS_32") (pintype "bidirectional"))
    )
    (net (code "15") (name "/DRV8323_MISO") (class "Default")
      (node (ref "U1") (pin "22") (pinfunction "PA6/TIM3_1/SPI1_MISO/I2S2_MCK/TIM13_1_22") (pintype "bidirectional"))
      (node (ref "U2") (pin "29") (pinfunction "MISO_29") (pintype "bidirectional"))
    )
    (net (code "16") (name "/DRV8323_MOSI") (class "Default")
      (node (ref "U1") (pin "23") (pinfunction "PA7/TIM1_1N/TIM3_2/TIM8_1N/SPI1_MOSI/I2S1_SD/TIM14_1_23") (pintype "bidirectional"))
      (node (ref "U2") (pin "30") (pinfunction "MOSI_30") (pintype "bidirectional"))
    )
    (net (code "17") (name "/DRV8323_SCLK") (class "Default")
      (node (ref "U1") (pin "21") (pinfunction "PA5/TIM2_1/TIM8_1N/SPI1_SCK/I2S1_CK_21") (pintype "bidirectional"))
      (node (ref "U2") (pin "31") (pinfunction "SCLK_31") (pintype "bidirectional"))
    )
    (net (code "18") (name "/GHA") (class "Default")
      (node (ref "Q1") (pin "4") (pinfunction "G_4") (pintype "passive"))
      (node (ref "U2") (pin "8") (pinfunction "GHA_8") (pintype "bidirectional"))
    )
    (net (code "19") (name "/GHB") (class "Default")
      (node (ref "Q3") (pin "4") (pinfunction "G_4") (pintype "passive"))
      (node (ref "U2") (pin "17") (pinfunction "GHB_17") (pintype "bidirectional"))
    )
    (net (code "20") (name "/GHC") (class "Default")
      (node (ref "Q5") (pin "4") (pinfunction "G_4") (pintype "passive"))
      (node (ref "U2") (pin "18") (pinfunction "GHC_18") (pintype "bidirectional"))
    )
    (net (code "21") (name "/GLA") (class "Default")
      (node (ref "Q2") (pin "4") (pinfunction "G_4") (pintype "passive"))
      (node (ref "U2") (pin "10") (pinfunction "GLA_10") (pintype "bidirectional"))
    )
    (net (code "22") (name "/GLB") (class "Default")
      (node (ref "Q4") (pin "4") (pinfunction "G_4") (pintype "passive"))
      (node (ref "U2") (pin "15") (pinfunction "GLB_15") (pintype "bidirectional"))
    )
    (net (code "23") (name "/GLC") (class "Default")
      (node (ref "Q6") (pin "4") (pinfunction "G_4") (pintype "passive"))
      (node (ref "U2") (pin "20") (pinfunction "GLC_20") (pintype "bidirectional"))
    )
    (net (code "24") (name "/I2C_ABS_SCL") (class "Default")
      (node (ref "ABS_SCL") (pin "P$1") (pinfunction "P$1_P$1") (pintype "bidirectional"))
      (node (ref "U1") (pin "61") (pinfunction "PB8/TIM2_1/TIM4_3/TIM10_1/I2C1_SCL_61") (pintype "bidirectional"))
    )
    (net (code "25") (name "/I2C_ABS_SDA") (class "Default")
      (node (ref "ABS_SDA") (pin "P$1") (pinfunction "P$1_P$1") (pintype "bidirectional"))
      (node (ref "U1") (pin "62") (pinfunction "PB9/TIM2_2/TIM4_4/TIM11_1/I2C1_SDA_62") (pintype "bidirectional"))
    )
    (net (code "26") (name "/LED1") (class "Default")
      (node (ref "D3") (pin "CATHODE") (pinfunction "CATHODE_CATHODE") (pintype "power_in"))
      (node (ref "U1") (pin "44") (pinfunction "PA11/TIM1_4/USB_DM_44") (pintype "bidirectional"))
    )
    (net (code "27") (name "/LED2") (class "Default")
      (node (ref "D2") (pin "CATHODE") (pinfunction "CATHODE_CATHODE") (pintype "power_in"))
      (node (ref "U1") (pin "45") (pinfunction "PA12/USART1_RTS/USB_DP_45") (pintype "bidirectional"))
    )
    (net (code "28") (name "/MOTOR1") (class "Default")
      (node (ref "U1") (pin "14") (pinfunction "PA0WKUP/TIM2_1/TIM5_1/UART4_TX_14") (pintype "bidirectional"))
      (node (ref "U2") (pin "37") (pinfunction "INHA_37") (pintype "bidirectional"))
    )
    (net (code "29") (name "/MOTOR2") (class "Default")
      (node (ref "U1") (pin "15") (pinfunction "PA1/TIM2_2/TIM5_2/UART4_RX_15") (pintype "bidirectional"))
      (node (ref "U2") (pin "39") (pinfunction "INHB_39") (pintype "bidirectional"))
    )
    (net (code "30") (name "/MOTOR3") (class "Default")
      (node (ref "M3") (pin "P$1") (pinfunction "P$1_P$1") (pintype "bidirectional"))
      (node (ref "U1") (pin "16") (pinfunction "PA2/TIM2_3/TIM5_3/TIM9_1/UART2_TX_16") (pintype "bidirectional"))
      (node (ref "U2") (pin "41") (pinfunction "INHC_41") (pintype "bidirectional"))
    )
    (net (code "31") (name "/MOTOR_ENABLE") (class "Default")
      (node (ref "U1") (pin "17") (pinfunction "PA3/TIM2_4/TIM5_4/TIM9_2/UART2_RX_17") (pintype "bidirectional"))
      (node (ref "U2") (pin "33") (pinfunction "ENABLE_33") (pintype "bidirectional"))
    )
    (net (code "32") (name "/MOTOR_FAULT") (class "Default")
      (node (ref "U1") (pin "24") (pinfunction "PC4/I2S1_MCK_24") (pintype "bidirectional"))
      (node (ref "U2") (pin "28") (pinfunction "FAULT_28") (pintype "bidirectional"))
    )
    (net (code "33") (name "/MOTOR_HIZ") (class "Default")
      (node (ref "U1") (pin "11") (pinfunction "PC3/SPI2_MOSI/I2S2_SD_11") (pintype "bidirectional"))
      (node (ref "U2") (pin "38") (pinfunction "INLA_38") (pintype "bidirectional"))
      (node (ref "U2") (pin "40") (pinfunction "INLB_40") (pintype "bidirectional"))
      (node (ref "U2") (pin "42") (pinfunction "INLC_42") (pintype "bidirectional"))
    )
    (net (code "34") (name "/RS485_DIR") (class "Default")
      (node (ref "U1") (pin "41") (pinfunction "PA8/TIM1_1/I2C3_SCL_41") (pintype "bidirectional"))
      (node (ref "U4") (pin "3") (pinfunction "DE_3") (pintype "bidirectional"))
      (node (ref "U4") (pin "4") (pinfunction "RE/_4") (pintype "bidirectional"))
    )
    (net (code "35") (name "/RS485_RX") (class "Default")
      (node (ref "U1") (pin "43") (pinfunction "PA10/TIM1_3/USART1_RX_43") (pintype "bidirectional"))
      (node (ref "U4") (pin "2") (pinfunction "RO_2") (pintype "bidirectional"))
    )
    (net (code "36") (name "/RS485_TX") (class "Default")
      (node (ref "U1") (pin "42") (pinfunction "PA9/TIM1_2/SPI2_SCK/I2S3_CK/UART1_TX/USB_VBUS_42") (pintype "bidirectional"))
      (node (ref "U4") (pin "5") (pinfunction "DI_5") (pintype "bidirectional"))
    )
    (net (code "37") (name "/SHA") (class "Default")
      (node (ref "A") (pin "1") (pinfunction "P$1_1") (pintype "bidirectional"))
      (node (ref "DA") (pin "P$1") (pinfunction "P$1_P$1") (pintype "bidirectional"))
      (node (ref "Q1") (pin "1") (pinfunction "S_1") (pintype "passive"))
      (node (ref "Q1") (pin "2") (pinfunction "S_2") (pintype "passive"))
      (node (ref "Q1") (pin "3") (pinfunction "S_3") (pintype "passive"))
      (node (ref "Q2") (pin "5") (pinfunction "D_5") (pintype "passive"))
      (node (ref "Q2") (pin "6") (pinfunction "D_6") (pintype "passive"))
      (node (ref "Q2") (pin "7") (pinfunction "D_7") (pintype "passive"))
      (node (ref "Q2") (pin "8") (pinfunction "D_8") (pintype "passive"))
      (node (ref "Q2") (pin "PAD") (pinfunction "D_PAD") (pintype "passive"))
      (node (ref "U2") (pin "9") (pinfunction "SHA_9") (pintype "bidirectional"))
    )
    (net (code "38") (name "/SHB") (class "Default")
      (node (ref "B") (pin "1") (pinfunction "P$1_1") (pintype "bidirectional"))
      (node (ref "DB") (pin "P$1") (pinfunction "P$1_P$1") (pintype "bidirectional"))
      (node (ref "Q3") (pin "1") (pinfunction "S_1") (pintype "passive"))
      (node (ref "Q3") (pin "2") (pinfunction "S_2") (pintype "passive"))
      (node (ref "Q3") (pin "3") (pinfunction "S_3") (pintype "passive"))
      (node (ref "Q4") (pin "5") (pinfunction "D_5") (pintype "passive"))
      (node (ref "Q4") (pin "6") (pinfunction "D_6") (pintype "passive"))
      (node (ref "Q4") (pin "7") (pinfunction "D_7") (pintype "passive"))
      (node (ref "Q4") (pin "8") (pinfunction "D_8") (pintype "passive"))
      (node (ref "Q4") (pin "PAD") (pinfunction "D_PAD") (pintype "passive"))
      (node (ref "U2") (pin "16") (pinfunction "SHB_16") (pintype "bidirectional"))
    )
    (net (code "39") (name "/SHC") (class "Default")
      (node (ref "C") (pin "1") (pinfunction "P$1_1") (pintype "bidirectional"))
      (node (ref "DC") (pin "P$1") (pinfunction "P$1_P$1") (pintype "bidirectional"))
      (node (ref "Q5") (pin "1") (pinfunction "S_1") (pintype "passive"))
      (node (ref "Q5") (pin "2") (pinfunction "S_2") (pintype "passive"))
      (node (ref "Q5") (pin "3") (pinfunction "S_3") (pintype "passive"))
      (node (ref "Q6") (pin "5") (pinfunction "D_5") (pintype "passive"))
      (node (ref "Q6") (pin "6") (pinfunction "D_6") (pintype "passive"))
      (node (ref "Q6") (pin "7") (pinfunction "D_7") (pintype "passive"))
      (node (ref "Q6") (pin "8") (pinfunction "D_8") (pintype "passive"))
      (node (ref "Q6") (pin "PAD") (pinfunction "D_PAD") (pintype "passive"))
      (node (ref "U2") (pin "19") (pinfunction "SHC_19") (pintype "bidirectional"))
    )
    (net (code "40") (name "/SNA") (class "Default")
      (node (ref "SH1") (pin "1") (pinfunction "P$1_1") (pintype "bidirectional"))
      (node (ref "U2") (pin "12") (pinfunction "SNA_12") (pintype "bidirectional"))
    )
    (net (code "41") (name "/SNB") (class "Default")
      (node (ref "SH2") (pin "1") (pinfunction "P$1_1") (pintype "bidirectional"))
      (node (ref "U2") (pin "13") (pinfunction "SNB_13") (pintype "bidirectional"))
    )
    (net (code "42") (name "/SNC") (class "Default")
      (node (ref "SH3") (pin "1") (pinfunction "P$1_1") (pintype "bidirectional"))
      (node (ref "U2") (pin "22") (pinfunction "SNC_22") (pintype "bidirectional"))
    )
    (net (code "43") (name "/SPA") (class "Default")
      (node (ref "Q2") (pin "1") (pinfunction "S_1") (pintype "passive"))
      (node (ref "Q2") (pin "2") (pinfunction "S_2") (pintype "passive"))
      (node (ref "Q2") (pin "3") (pinfunction "S_3") (pintype "passive"))
      (node (ref "RA") (pin "2") (pinfunction "2_2") (pintype "passive"))
      (node (ref "U2") (pin "11") (pinfunction "SPA_11") (pintype "bidirectional"))
    )
    (net (code "44") (name "/SPB") (class "Default")
      (node (ref "Q4") (pin "1") (pinfunction "S_1") (pintype "passive"))
      (node (ref "Q4") (pin "2") (pinfunction "S_2") (pintype "passive"))
      (node (ref "Q4") (pin "3") (pinfunction "S_3") (pintype "passive"))
      (node (ref "RB") (pin "2") (pinfunction "2_2") (pintype "passive"))
      (node (ref "U2") (pin "14") (pinfunction "SPB_14") (pintype "bidirectional"))
    )
    (net (code "45") (name "/SPC") (class "Default")
      (node (ref "Q6") (pin "1") (pinfunction "S_1") (pintype "passive"))
      (node (ref "Q6") (pin "2") (pinfunction "S_2") (pintype "passive"))
      (node (ref "Q6") (pin "3") (pinfunction "S_3") (pintype "passive"))
      (node (ref "RC") (pin "2") (pinfunction "2_2") (pintype "passive"))
      (node (ref "U2") (pin "21") (pinfunction "SPC_21") (pintype "bidirectional"))
    )
    (net (code "46") (name "/VBAT_SENSE") (class "Default")
      (node (ref "R7") (pin "P$1") (pinfunction "P$1_P$1") (pintype "passive"))
      (node (ref "R8") (pin "P$2") (pinfunction "P$2_P$2") (pintype "passive"))
      (node (ref "U1") (pin "9") (pinfunction "PC1/SPI3_MOSI/I2S3_SD/SPI2_MOSI/I2S2_SD_9") (pintype "bidirectional"))
    )
    (net (code "47") (name "/VTEMP_FET") (class "Default")
      (node (ref "C32") (pin "P$1") (pinfunction "P$1_P$1") (pintype "passive"))
      (node (ref "R12") (pin "P$2") (pinfunction "P$2_P$2") (pintype "passive"))
      (node (ref "R13") (pin "P$1") (pinfunction "P$1_P$1") (pintype "passive"))
      (node (ref "U1") (pin "10") (pinfunction "PC2/SPI2_MISO_10") (pintype "bidirectional"))
    )
    (net (code "48") (name "/VTEMP_MOT") (class "Default")
      (node (ref "R5") (pin "P$1") (pinfunction "P$1_P$1") (pintype "passive"))
      (node (ref "TEMP2") (pin "P$1") (pinfunction "P$1_P$1") (pintype "bidirectional"))
      (node (ref "U1") (pin "8") (pinfunction "PC0_8") (pintype "bidirectional"))
    )
    (net (code "49") (name "GND") (class "Default")
      (node (ref "ABS_GND") (pin "P$1") (pinfunction "P$1_P$1") (pintype "bidirectional"))
      (node (ref "C1") (pin "P$2") (pinfunction "P$2_P$2") (pintype "passive"))
      (node (ref "C10") (pin "P$2") (pinfunction "P$2_P$2") (pintype "passive"))
      (node (ref "C11") (pin "P$2") (pinfunction "P$2_P$2") (pintype "passive"))
      (node (ref "C12") (pin "P$2") (pinfunction "P$2_P$2") (pintype "passive"))
      (node (ref "C2") (pin "P$2") (pinfunction "P$2_P$2") (pintype "passive"))
      (node (ref "C20") (pin "P$2") (pinfunction "P$2_P$2") (pintype "passive"))
      (node (ref "C24") (pin "P$1") (pinfunction "P$1_P$1") (pintype "passive"))
      (node (ref "C25") (pin "P$1") (pinfunction "P$1_P$1") (pintype "passive"))
      (node (ref "C26") (pin "P$2") (pinfunction "P$2_P$2") (pintype "passive"))
      (node (ref "C27") (pin "P$2") (pinfunction "P$2_P$2") (pintype "passive"))
      (node (ref "C29") (pin "P$2") (pinfunction "P$2_P$2") (pintype "passive"))
      (node (ref "C3") (pin "P$2") (pinfunction "P$2_P$2") (pintype "passive"))
      (node (ref "C30") (pin "P$2") (pinfunction "P$2_P$2") (pintype "passive"))
      (node (ref "C31") (pin "P$2") (pinfunction "P$2_P$2") (pintype "passive"))
      (node (ref "C32") (pin "P$2") (pinfunction "P$2_P$2") (pintype "passive"))
      (node (ref "C4") (pin "P$2") (pinfunction "P$2_P$2") (pintype "passive"))
      (node (ref "C5") (pin "P$2") (pinfunction "P$2_P$2") (pintype "passive"))
      (node (ref "C6") (pin "P$2") (pinfunction "P$2_P$2") (pintype "passive"))
      (node (ref "C7") (pin "P$2") (pinfunction "P$2_P$2") (pintype "passive"))
      (node (ref "C8") (pin "P$2") (pinfunction "P$2_P$2") (pintype "passive"))
      (node (ref "C9") (pin "P$2") (pinfunction "P$2_P$2") (pintype "passive"))
      (node (ref "DGND") (pin "P$1") (pinfunction "P$1_P$1") (pintype "bidirectional"))
      (node (ref "J1") (pin "3") (pinfunction "3_3") (pintype "passive"))
      (node (ref "J2") (pin "3") (pinfunction "3_3") (pintype "passive"))
      (node (ref "LNK") (pin "1") (pinfunction "1_1") (pintype "passive"))
      (node (ref "R1") (pin "P$1") (pinfunction "P$1_P$1") (pintype "passive"))
      (node (ref "R13") (pin "P$2") (pinfunction "P$2_P$2") (pintype "passive"))
      (node (ref "R5") (pin "P$2") (pinfunction "P$2_P$2") (pintype "passive"))
      (node (ref "R8") (pin "P$1") (pinfunction "P$1_P$1") (pintype "passive"))
      (node (ref "SH4") (pin "2") (pinfunction "P$2_2") (pintype "bidirectional"))
      (node (ref "SWD") (pin "4") (pinfunction "4_4") (pintype "passive"))
      (node (ref "U1") (pin "12") (pinfunction "VSSA_12") (pintype "bidirectional"))
      (node (ref "U1") (pin "18") (pinfunction "VSS1_18") (pintype "bidirectional"))
      (node (ref "U1") (pin "3") (pinfunction "PC14_3") (pintype "bidirectional"))
      (node (ref "U1") (pin "31") (pinfunction "VSS4_31") (pintype "bidirectional"))
      (node (ref "U1") (pin "47") (pinfunction "VSS3_47") (pintype "bidirectional"))
      (node (ref "U1") (pin "63") (pinfunction "VSS2_63") (pintype "bidirectional"))
      (node (ref "U2") (pin "27") (pinfunction "DGND_27") (pintype "bidirectional"))
      (node (ref "U2") (pin "35") (pinfunction "AGND_35") (pintype "bidirectional"))
      (node (ref "U3") (pin "13") (pinfunction "GND_13") (pintype "bidirectional"))
      (node (ref "U3") (pin "5") (pinfunction "TEST_5") (pintype "bidirectional"))
      (node (ref "U4") (pin "6") (pinfunction "GND_6") (pintype "bidirectional"))
      (node (ref "U4") (pin "PAD") (pinfunction "GND_PAD") (pintype "bidirectional"))
      (node (ref "U5") (pin "15") (pinfunction "EP_15") (pintype "power_in"))
      (node (ref "U5") (pin "4") (pinfunction "~{RE}_4") (pintype "input"))
      (node (ref "U5") (pin "6") (pinfunction "GND_2_6") (pintype "power_in"))
      (node (ref "U5") (pin "8") (pinfunction "GND_8") (pintype "power_in"))
      (node (ref "X1") (pin "2") (pinfunction "P$3_2") (pintype "bidirectional"))
      (node (ref "X1") (pin "4") (pinfunction "P$3_4") (pintype "bidirectional"))
    )
    (net (code "50") (name "Net-(D2-PadANODE)") (class "Default")
      (node (ref "D2") (pin "ANODE") (pinfunction "ANODE_ANODE") (pintype "power_in"))
      (node (ref "R9") (pin "P$2") (pinfunction "P$2_P$2") (pintype "passive"))
    )
    (net (code "51") (name "Net-(D3-PadANODE)") (class "Default")
      (node (ref "D3") (pin "ANODE") (pinfunction "ANODE_ANODE") (pintype "power_in"))
      (node (ref "R6") (pin "P$2") (pinfunction "P$2_P$2") (pintype "passive"))
    )
    (net (code "52") (name "Net-(U1-BOOT0)") (class "Default")
      (node (ref "R1") (pin "P$2") (pinfunction "P$2_P$2") (pintype "passive"))
      (node (ref "U1") (pin "60") (pinfunction "BOOT0_60") (pintype "bidirectional"))
    )
    (net (code "53") (name "Net-(U1-NRST)") (class "Default")
      (node (ref "C6") (pin "P$1") (pinfunction "P$1_P$1") (pintype "passive"))
      (node (ref "SWD") (pin "2") (pinfunction "2_2") (pintype "passive"))
      (node (ref "U1") (pin "7") (pinfunction "NRST_7") (pintype "bidirectional"))
    )
    (net (code "54") (name "Net-(U1-PA4)") (class "Default")
      (node (ref "DAC1") (pin "P$1") (pinfunction "P$1_P$1") (pintype "bidirectional"))
      (node (ref "U1") (pin "20") (pinfunction "PA4_20") (pintype "bidirectional"))
    )
    (net (code "55") (name "Net-(U1-PA13{slash}SWDIO)") (class "Default")
      (node (ref "SWD") (pin "3") (pinfunction "3_3") (pintype "passive"))
      (node (ref "U1") (pin "46") (pinfunction "PA13/SWDIO_46") (pintype "bidirectional"))
    )
    (net (code "56") (name "Net-(U1-PA14{slash}SWCLK)") (class "Default")
      (node (ref "SWD") (pin "5") (pinfunction "5_5") (pintype "passive"))
      (node (ref "U1") (pin "49") (pinfunction "PA14/SWCLK_49") (pintype "bidirectional"))
    )
    (net (code "57") (name "Net-(U1-PB6{slash}TIM4_1{slash}I2C1_SCL{slash}UART1_TX)") (class "Default")
      (node (ref "DTX") (pin "P$1") (pinfunction "P$1_P$1") (pintype "bidirectional"))
      (node (ref "U1") (pin "58") (pinfunction "PB6/TIM4_1/I2C1_SCL/UART1_TX_58") (pintype "bidirectional"))
    )
    (net (code "58") (name "Net-(U1-PB7{slash}TIM4_2{slash}I2C1_SDA{slash}UART1_RX)") (class "Default")
      (node (ref "DRX") (pin "P$1") (pinfunction "P$1_P$1") (pintype "bidirectional"))
      (node (ref "U1") (pin "59") (pinfunction "PB7/TIM4_2/I2C1_SDA/UART1_RX_59") (pintype "bidirectional"))
    )
    (net (code "59") (name "Net-(U1-PH0)") (class "Default")
      (node (ref "C8") (pin "P$1") (pinfunction "P$1_P$1") (pintype "passive"))
      (node (ref "U1") (pin "5") (pinfunction "PH0_5") (pintype "bidirectional"))
      (node (ref "X1") (pin "1") (pinfunction "P$1_1") (pintype "bidirectional"))
    )
    (net (code "60") (name "Net-(U1-PH1)") (class "Default")
      (node (ref "C9") (pin "P$1") (pinfunction "P$1_P$1") (pintype "passive"))
      (node (ref "U1") (pin "6") (pinfunction "PH1_6") (pintype "bidirectional"))
      (node (ref "X1") (pin "3") (pinfunction "P$2_3") (pintype "bidirectional"))
    )
    (net (code "61") (name "Net-(U1-VCAP1)") (class "Default")
      (node (ref "C7") (pin "P$1") (pinfunction "P$1_P$1") (pintype "passive"))
      (node (ref "U1") (pin "30") (pinfunction "VCAP1_30") (pintype "bidirectional"))
    )
    (net (code "62") (name "Net-(U2-CB)") (class "Default")
      (node (ref "C21") (pin "P$1") (pinfunction "P$1_P$1") (pintype "passive"))
      (node (ref "U2") (pin "44") (pinfunction "CB_44") (pintype "bidirectional"))
    )
    (net (code "63") (name "Net-(U2-CPH)") (class "Default")
      (node (ref "C22") (pin "P$1") (pinfunction "P$1_P$1") (pintype "passive"))
      (node (ref "U2") (pin "4") (pinfunction "CPH_4") (pintype "bidirectional"))
    )
    (net (code "64") (name "Net-(U2-CPL)") (class "Default")
      (node (ref "C22") (pin "P$2") (pinfunction "P$2_P$2") (pintype "passive"))
      (node (ref "U2") (pin "3") (pinfunction "CPL_3") (pintype "bidirectional"))
    )
    (net (code "65") (name "Net-(U2-DVDD)") (class "Default")
      (node (ref "C25") (pin "P$2") (pinfunction "P$2_P$2") (pintype "passive"))
      (node (ref "U2") (pin "36") (pinfunction "DVDD_36") (pintype "bidirectional"))
    )
    (net (code "66") (name "Net-(U2-FB)") (class "Default")
      (node (ref "R11") (pin "P$2") (pinfunction "P$2_P$2") (pintype "passive"))
      (node (ref "R4") (pin "P$1") (pinfunction "P$1_P$1") (pintype "passive"))
      (node (ref "U2") (pin "1") (pinfunction "FB_1") (pintype "bidirectional"))
    )
    (net (code "67") (name "Net-(U2-SHDN)") (class "Default")
      (node (ref "R2") (pin "P$1") (pinfunction "P$1_P$1") (pintype "passive"))
      (node (ref "U2") (pin "48") (pinfunction "SHDN_48") (pintype "bidirectional"))
    )
    (net (code "68") (name "Net-(U2-SW)") (class "Default")
      (node (ref "C21") (pin "P$2") (pinfunction "P$2_P$2") (pintype "passive"))
      (node (ref "D1") (pin "CATHODE") (pinfunction "CATHODE_CATHODE") (pintype "bidirectional"))
      (node (ref "L1") (pin "2") (pinfunction "2_2") (pintype "passive"))
      (node (ref "U2") (pin "45") (pinfunction "SW_45") (pintype "bidirectional"))
    )
    (net (code "69") (name "Net-(U2-VCP)") (class "Default")
      (node (ref "C23") (pin "P$2") (pinfunction "P$2_P$2") (pintype "passive"))
      (node (ref "U2") (pin "5") (pinfunction "VCP_5") (pintype "bidirectional"))
    )
    (net (code "70") (name "Net-(U4-A)") (class "Default")
      (node (ref "J1") (pin "1") (pinfunction "1_1") (pintype "passive"))
      (node (ref "J2") (pin "1") (pinfunction "1_1") (pintype "passive"))
      (node (ref "U4") (pin "8") (pinfunction "A_8") (pintype "bidirectional"))
    )
    (net (code "71") (name "Net-(U4-B)") (class "Default")
      (node (ref "J1") (pin "2") (pinfunction "2_2") (pintype "passive"))
      (node (ref "J2") (pin "2") (pinfunction "2_2") (pintype "passive"))
      (node (ref "U4") (pin "9") (pinfunction "B_9") (pintype "bidirectional"))
    )
    (net (code "72") (name "Net-(U5-A)") (class "Default")
      (node (ref "LNK") (pin "5") (pinfunction "5_5") (pintype "passive"))
      (node (ref "U5") (pin "12") (pinfunction "A_12") (pintype "passive"))
    )
    (net (code "73") (name "Net-(U5-B)") (class "Default")
      (node (ref "LNK") (pin "4") (pinfunction "4_4") (pintype "passive"))
      (node (ref "U5") (pin "11") (pinfunction "B_11") (pintype "input"))
    )
    (net (code "74") (name "Net-(U5-Y)") (class "Default")
      (node (ref "LNK") (pin "2") (pinfunction "2_2") (pintype "passive"))
      (node (ref "U5") (pin "9") (pinfunction "Y_9") (pintype "output"))
    )
    (net (code "75") (name "Net-(U5-Z)") (class "Default")
      (node (ref "LNK") (pin "3") (pinfunction "3_3") (pintype "passive"))
      (node (ref "U5") (pin "10") (pinfunction "Z_10") (pintype "output"))
    )
    (net (code "76") (name "V+") (class "Default")
      (node (ref "C13") (pin "P$1") (pinfunction "P$1_P$1") (pintype "passive"))
      (node (ref "C14") (pin "P$1") (pinfunction "P$1_P$1") (pintype "passive"))
      (node (ref "C15") (pin "P$1") (pinfunction "P$1_P$1") (pintype "passive"))
      (node (ref "C16") (pin "P$1") (pinfunction "P$1_P$1") (pintype "passive"))
      (node (ref "C17") (pin "P$1") (pinfunction "P$1_P$1") (pintype "passive"))
      (node (ref "C18") (pin "P$1") (pinfunction "P$1_P$1") (pintype "passive"))
      (node (ref "C19") (pin "P$1") (pinfunction "P$1_P$1") (pintype "passive"))
      (node (ref "C23") (pin "P$1") (pinfunction "P$1_P$1") (pintype "passive"))
      (node (ref "C28") (pin "P$1") (pinfunction "P$1_P$1") (pintype "passive"))
      (node (ref "C33") (pin "P$1") (pinfunction "P$1_P$1") (pintype "passive"))
      (node (ref "C34") (pin "P$1") (pinfunction "P$1_P$1") (pintype "passive"))
      (node (ref "C35") (pin "P$1") (pinfunction "P$1_P$1") (pintype "passive"))
      (node (ref "C36") (pin "P$1") (pinfunction "P$1_P$1") (pintype "passive"))
      (node (ref "C37") (pin "P$1") (pinfunction "P$1_P$1") (pintype "passive"))
      (node (ref "C38") (pin "P$1") (pinfunction "P$1_P$1") (pintype "passive"))
      (node (ref "Q1") (pin "5") (pinfunction "D_5") (pintype "passive"))
      (node (ref "Q1") (pin "6") (pinfunction "D_6") (pintype "passive"))
      (node (ref "Q1") (pin "7") (pinfunction "D_7") (pintype "passive"))
      (node (ref "Q1") (pin "8") (pinfunction "D_8") (pintype "passive"))
      (node (ref "Q1") (pin "PAD") (pinfunction "D_PAD") (pintype "passive"))
      (node (ref "Q3") (pin "5") (pinfunction "D_5") (pintype "passive"))
      (node (ref "Q3") (pin "6") (pinfunction "D_6") (pintype "passive"))
      (node (ref "Q3") (pin "7") (pinfunction "D_7") (pintype "passive"))
      (node (ref "Q3") (pin "8") (pinfunction "D_8") (pintype "passive"))
      (node (ref "Q3") (pin "PAD") (pinfunction "D_PAD") (pintype "passive"))
      (node (ref "Q5") (pin "5") (pinfunction "D_5") (pintype "passive"))
      (node (ref "Q5") (pin "6") (pinfunction "D_6") (pintype "passive"))
      (node (ref "Q5") (pin "7") (pinfunction "D_7") (pintype "passive"))
      (node (ref "Q5") (pin "8") (pinfunction "D_8") (pintype "passive"))
      (node (ref "Q5") (pin "PAD") (pinfunction "D_PAD") (pintype "passive"))
      (node (ref "R2") (pin "P$2") (pinfunction "P$2_P$2") (pintype "passive"))
      (node (ref "R7") (pin "P$2") (pinfunction "P$2_P$2") (pintype "passive"))
      (node (ref "U2") (pin "47") (pinfunction "VIN_47") (pintype "bidirectional"))
      (node (ref "U2") (pin "6") (pinfunction "VM_6") (pintype "bidirectional"))
      (node (ref "U2") (pin "7") (pinfunction "VDRAIN_7") (pintype "bidirectional"))
      (node (ref "V+") (pin "1") (pinfunction "P$1_1") (pintype "bidirectional"))
    )
    (net (code "77") (name "V-") (class "Default")
      (node (ref "C13") (pin "P$2") (pinfunction "P$2_P$2") (pintype "passive"))
      (node (ref "C14") (pin "P$2") (pinfunction "P$2_P$2") (pintype "passive"))
      (node (ref "C15") (pin "P$2") (pinfunction "P$2_P$2") (pintype "passive"))
      (node (ref "C16") (pin "P$2") (pinfunction "P$2_P$2") (pintype "passive"))
      (node (ref "C17") (pin "P$2") (pinfunction "P$2_P$2") (pintype "passive"))
      (node (ref "C18") (pin "P$2") (pinfunction "P$2_P$2") (pintype "passive"))
      (node (ref "C19") (pin "P$2") (pinfunction "P$2_P$2") (pintype "passive"))
      (node (ref "C28") (pin "P$2") (pinfunction "P$2_P$2") (pintype "passive"))
      (node (ref "C33") (pin "P$2") (pinfunction "P$2_P$2") (pintype "passive"))
      (node (ref "C34") (pin "P$2") (pinfunction "P$2_P$2") (pintype "passive"))
      (node (ref "C35") (pin "P$2") (pinfunction "P$2_P$2") (pintype "passive"))
      (node (ref "C36") (pin "P$2") (pinfunction "P$2_P$2") (pintype "passive"))
      (node (ref "C37") (pin "P$2") (pinfunction "P$2_P$2") (pintype "passive"))
      (node (ref "C38") (pin "P$2") (pinfunction "P$2_P$2") (pintype "passive"))
      (node (ref "D1") (pin "ANODE") (pinfunction "ANODE_ANODE") (pintype "bidirectional"))
      (node (ref "R4") (pin "P$2") (pinfunction "P$2_P$2") (pintype "passive"))
      (node (ref "RA") (pin "1") (pinfunction "1_1") (pintype "passive"))
      (node (ref "RB") (pin "1") (pinfunction "1_1") (pintype "passive"))
      (node (ref "RC") (pin "1") (pinfunction "1_1") (pintype "passive"))
      (node (ref "SH1") (pin "2") (pinfunction "P$2_2") (pintype "bidirectional"))
      (node (ref "SH2") (pin "2") (pinfunction "P$2_2") (pintype "bidirectional"))
      (node (ref "SH3") (pin "2") (pinfunction "P$2_2") (pintype "bidirectional"))
      (node (ref "SH4") (pin "1") (pinfunction "P$1_1") (pintype "bidirectional"))
      (node (ref "U2") (pin "2") (pinfunction "PGND_2") (pintype "bidirectional"))
      (node (ref "U2") (pin "43") (pinfunction "BGND_43") (pintype "bidirectional"))
      (node (ref "U2") (pin "P1") (pinfunction "PAD_P1") (pintype "bidirectional"))
      (node (ref "U2") (pin "P10") (pinfunction "PAD_P10") (pintype "bidirectional"))
      (node (ref "U2") (pin "P11") (pinfunction "PAD_P11") (pintype "bidirectional"))
      (node (ref "U2") (pin "P12") (pinfunction "PAD_P12") (pintype "bidirectional"))
      (node (ref "U2") (pin "P13") (pinfunction "PAD_P13") (pintype "bidirectional"))
      (node (ref "U2") (pin "P14") (pinfunction "PAD_P14") (pintype "bidirectional"))
      (node (ref "U2") (pin "P15") (pinfunction "PAD_P15") (pintype "bidirectional"))
      (node (ref "U2") (pin "P16") (pinfunction "PAD_P16") (pintype "bidirectional"))
      (node (ref "U2") (pin "P17") (pinfunction "PAD_P17") (pintype "bidirectional"))
      (node (ref "U2") (pin "P18") (pinfunction "PAD_P18") (pintype "bidirectional"))
      (node (ref "U2") (pin "P19") (pinfunction "PAD_P19") (pintype "bidirectional"))
      (node (ref "U2") (pin "P2") (pinfunction "PAD_P2") (pintype "bidirectional"))
      (node (ref "U2") (pin "P20") (pinfunction "PAD_P20") (pintype "bidirectional"))
      (node (ref "U2") (pin "P21") (pinfunction "PAD_P21") (pintype "bidirectional"))
      (node (ref "U2") (pin "P22") (pinfunction "PAD_P22") (pintype "bidirectional"))
      (node (ref "U2") (pin "P23") (pinfunction "PAD_P23") (pintype "bidirectional"))
      (node (ref "U2") (pin "P24") (pinfunction "PAD_P24") (pintype "bidirectional"))
      (node (ref "U2") (pin "P25") (pinfunction "PAD_P25") (pintype "bidirectional"))
      (node (ref "U2") (pin "P3") (pinfunction "PAD_P3") (pintype "bidirectional"))
      (node (ref "U2") (pin "P4") (pinfunction "PAD_P4") (pintype "bidirectional"))
      (node (ref "U2") (pin "P5") (pinfunction "PAD_P5") (pintype "bidirectional"))
      (node (ref "U2") (pin "P6") (pinfunction "PAD_P6") (pintype "bidirectional"))
      (node (ref "U2") (pin "P7") (pinfunction "PAD_P7") (pintype "bidirectional"))
      (node (ref "U2") (pin "P8") (pinfunction "PAD_P8") (pintype "bidirectional"))
      (node (ref "U2") (pin "P9") (pinfunction "PAD_P9") (pintype "bidirectional"))
      (node (ref "U2") (pin "PAD") (pinfunction "PAD_PAD") (pintype "bidirectional"))
      (node (ref "V-") (pin "1") (pinfunction "P$1_1") (pintype "bidirectional"))
    )
    (net (code "78") (name "unconnected-(SWD-Pad1)") (class "Default")
      (node (ref "SWD") (pin "1") (pinfunction "1_1") (pintype "passive"))
    )
    (net (code "79") (name "unconnected-(U1-PA15{slash}TIM2_1{slash}UART4_RTS-Pad50)") (class "Default")
      (node (ref "U1") (pin "50") (pinfunction "PA15/TIM2_1/UART4_RTS_50") (pintype "bidirectional"))
    )
    (net (code "80") (name "unconnected-(U1-PB2-BOOT1{slash}TIM2_4{slash}SPI3_MOSI{slash}I3S3_SD-Pad28)") (class "Default")
      (node (ref "U1") (pin "28") (pinfunction "PB2-BOOT1/TIM2_4/SPI3_MOSI/I3S3_SD_28") (pintype "bidirectional"))
    )
    (net (code "81") (name "unconnected-(U1-PB3{slash}SWO{slash}TIM2_2{slash}I2C2_SDA{slash}SPI1_SCK{slash}I2S1_CK{slash}SPI3_SCK{slash}I2S3_CK-Pad55)") (class "Default")
      (node (ref "U1") (pin "55") (pinfunction "PB3/SWO/TIM2_2/I2C2_SDA/SPI1_SCK/I2S1_CK/SPI3_SCK/I2S3_CK_55") (pintype "bidirectional"))
    )
    (net (code "82") (name "unconnected-(U1-PB4{slash}NJTRST{slash}TIM3_1{slash}I2C3_SDA{slash}SPI1_MISO{slash}SPI3_MISO-Pad56)") (class "Default")
      (node (ref "U1") (pin "56") (pinfunction "PB4/NJTRST/TIM3_1/I2C3_SDA/SPI1_MISO/SPI3_MISO_56") (pintype "bidirectional"))
    )
    (net (code "83") (name "unconnected-(U1-PB5{slash}TIM3_2{slash}SPI1_MOSI{slash}I2S1_SD{slash}SPI3_MOSI{slash}I2S3_SD-Pad57)") (class "Default")
      (node (ref "U1") (pin "57") (pinfunction "PB5/TIM3_2/SPI1_MOSI/I2S1_SD/SPI3_MOSI/I2S3_SD_57") (pintype "bidirectional"))
    )
    (net (code "84") (name "unconnected-(U1-PB10{slash}TIM2_3{slash}I2C2_SCL{slash}SPI3_SCK{slash}I2S2_CK{slash}UART3_TX-Pad29)") (class "Default")
      (node (ref "U1") (pin "29") (pinfunction "PB10/TIM2_3/I2C2_SCL/SPI3_SCK/I2S2_CK/UART3_TX_29") (pintype "bidirectional"))
    )
    (net (code "85") (name "unconnected-(U1-PC9{slash}TIM3_4{slash}TIM8_4{slash}I2C3_SDA-Pad40)") (class "Default")
      (node (ref "U1") (pin "40") (pinfunction "PC9/TIM3_4/TIM8_4/I2C3_SDA_40") (pintype "bidirectional"))
    )
    (net (code "86") (name "unconnected-(U1-PC12{slash}I2C2_SDA{slash}SPI3_MOSI{slash}I2S3_SD{slash}UART3_CK{slash}UART5_TX-Pad53)") (class "Default")
      (node (ref "U1") (pin "53") (pinfunction "PC12/I2C2_SDA/SPI3_MOSI/I2S3_SD/UART3_CK/UART5_TX_53") (pintype "bidirectional"))
    )
    (net (code "87") (name "unconnected-(U1-PC13-Pad2)") (class "Default")
      (node (ref "U1") (pin "2") (pinfunction "PC13_2") (pintype "bidirectional"))
    )
    (net (code "88") (name "unconnected-(U1-PC15-Pad4)") (class "Default")
      (node (ref "U1") (pin "4") (pinfunction "PC15_4") (pintype "bidirectional"))
    )
    (net (code "89") (name "unconnected-(U1-PD2-Pad54)") (class "Default")
      (node (ref "U1") (pin "54") (pinfunction "PD2_54") (pintype "bidirectional"))
    )
    (net (code "90") (name "unconnected-(U2-CAL-Pad34)") (class "Default")
      (node (ref "U2") (pin "34") (pinfunction "CAL_34") (pintype "bidirectional"))
    )
    (net (code "91") (name "unconnected-(U3-PWM-Pad8)") (class "Default")
      (node (ref "U3") (pin "8") (pinfunction "PWM_8") (pintype "bidirectional"))
    )
    (net (code "92") (name "unconnected-(U3-VDD5V-Pad11)") (class "Default")
      (node (ref "U3") (pin "11") (pinfunction "VDD5V_11") (pintype "bidirectional"))
    )
    (net (code "93") (name "unconnected-(U5-NC-Pad13)") (class "Default")
      (node (ref "U5") (pin "13") (pinfunction "NC_13") (pintype "no_connect"))
    )
    (net (code "94") (name "unconnected-(U5-NC_2-Pad7)") (class "Default")
      (node (ref "U5") (pin "7") (pinfunction "NC_2_7") (pintype "no_connect"))
    )
  )
)
